# DCDC.net
KiCad netlist of a schematic drawn in EasyEDA Pro
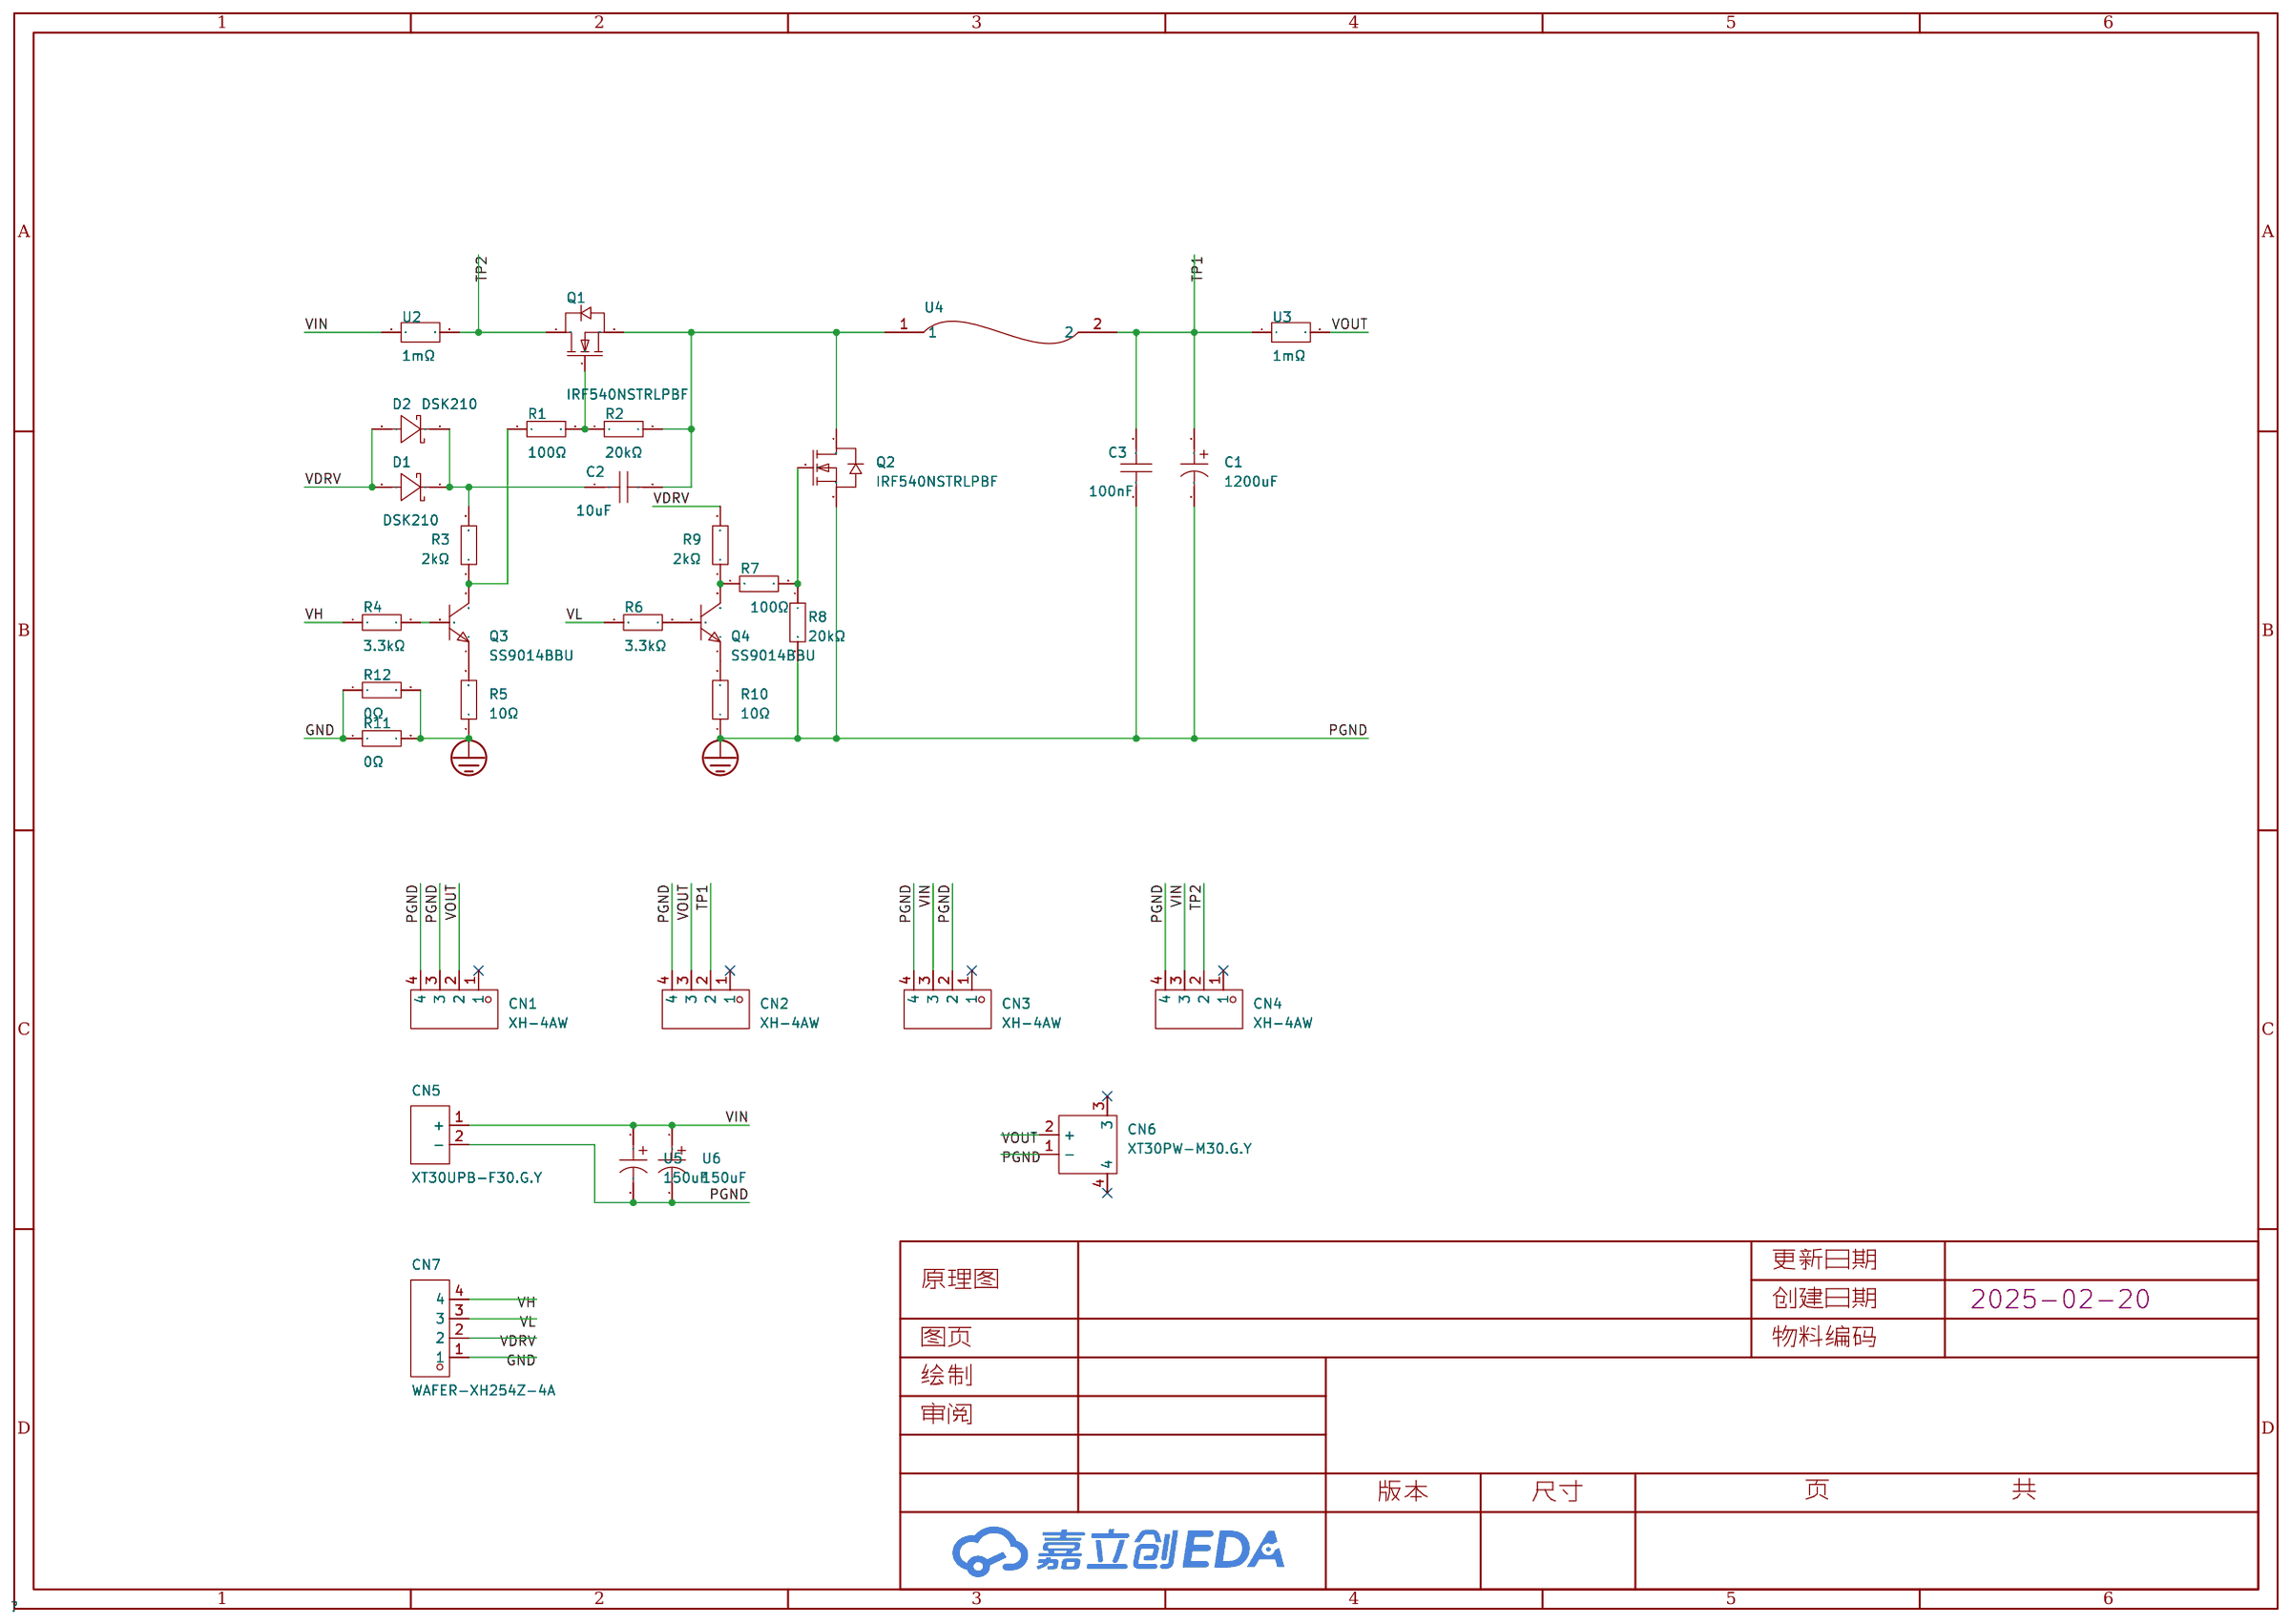
[diagram p0: schematic sheet]

(export (version "E")
  (design (tool "Eeschema 10.0.6"))
  (components
    (comp (ref "C1")
      (value "1200uF")
      (footprint "easyedapro:CAP-TH_BD18.0-P7.50-D0.8-FD")
      (description "容值:1200uF;精度:±20%;额定电压:63V;纹波电流:665mA@100kHz;等效串联电阻:160mΩ@100kHz;")
      (fields
        (field (name "Manufacturer Part") "NXA63V1200M18*31.5 LO")
        (field (name "Manufacturer") "SAMYOUNG(韩国三莹)")
      )
      (libsource (lib "easyedapro") (part "NXA63V1200M18*31.5 LO"))
    )
    (comp (ref "C2")
      (value "10uF")
      (footprint "easyedapro:C0805")
      (description "容值:10uF;精度:±10%;额定电压:50V;材质(温度系数):X5R;")
      (fields
        (field (name "Manufacturer Part") "GRM21BR61H106KE43L")
        (field (name "Manufacturer") "muRata(村田)")
      )
      (libsource (lib "easyedapro") (part "GRM21BR61H106KE43L"))
    )
    (comp (ref "C3")
      (value "100nF")
      (footprint "easyedapro:C0805")
      (description "容值:100nF;精度:±10%;额定电压:50V;材质(温度系数):X7R;")
      (fields
        (field (name "Manufacturer Part") "CC0805KRX7R9BB104")
        (field (name "Manufacturer") "YAGEO(国巨)")
      )
      (libsource (lib "easyedapro") (part "CC0805KRX7R9BB104"))
    )
    (comp (ref "CN1")
      (value "XH-4AW")
      (footprint "easyedapro:CONN-TH_XH-4AW")
      (fields (field (name "Manufacturer") "HCTL(华灿天禄)"))
      (libsource (lib "easyedapro") (part "XH-4AW_C2908613"))
    )
    (comp (ref "CN2")
      (value "XH-4AW")
      (footprint "easyedapro:CONN-TH_XH-4AW")
      (fields (field (name "Manufacturer") "HCTL(华灿天禄)"))
      (libsource (lib "easyedapro") (part "XH-4AW_C2908613"))
    )
    (comp (ref "CN3")
      (value "XH-4AW")
      (footprint "easyedapro:CONN-TH_XH-4AW")
      (fields (field (name "Manufacturer") "HCTL(华灿天禄)"))
      (libsource (lib "easyedapro") (part "XH-4AW_C2908613"))
    )
    (comp (ref "CN4")
      (value "XH-4AW")
      (footprint "easyedapro:CONN-TH_XH-4AW")
      (fields (field (name "Manufacturer") "HCTL(华灿天禄)"))
      (libsource (lib "easyedapro") (part "XH-4AW_C2908613"))
    )
    (comp (ref "CN5")
      (value "XT30UPB-F30.G.Y")
      (footprint "easyedapro:CONN-TH_XT30UPB-F")
      (description "类别:-;类型1:-;")
      (fields (field (name "Manufacturer") "AMASS(艾迈斯)"))
      (libsource (lib "easyedapro") (part "XT30UPB-F"))
    )
    (comp (ref "CN6")
      (value "XT30PW-M30.G.Y")
      (footprint "easyedapro:CONN-TH_XT30PW-M")
      (description "类别:-;类型1:-;")
      (fields (field (name "Manufacturer") "AMASS(艾迈斯)"))
      (libsource (lib "easyedapro") (part "XT30PW-M"))
    )
    (comp (ref "CN7")
      (value "WAFER-XH254Z-4A")
      (footprint "easyedapro:CONN-TH_XH-4A")
      (description "插针结构:1x4P;间距:2.54mm;安装方式:直插;参考系列:XH;总PIN数:4P;排数:1;每排PIN数:4;额定电流:3A;工作温度范围:-25°C~+85°C;")
      (fields (field (name "Manufacturer") "HANBO(汉博)"))
      (libsource (lib "easyedapro") (part "WAFER-XH254Z-4A"))
    )
    (comp (ref "D1")
      (value "DSK210")
      (footprint "easyedapro:SOD-123FL_L2.7-W1.8-LS3.8-RD")
      (description "二极管配置:独立式;正向压降(Vf):850mV@2A;直流反向耐压(Vr):100V;整流电流:2A;")
      (fields (field (name "Manufacturer") "宏迦橙"))
      (libsource (lib "easyedapro") (part "DSK210_C7502713"))
    )
    (comp (ref "D2")
      (value "DSK210")
      (footprint "easyedapro:SOD-123FL_L2.7-W1.8-LS3.8-RD")
      (description "二极管配置:独立式;正向压降(Vf):850mV@2A;直流反向耐压(Vr):100V;整流电流:2A;")
      (fields (field (name "Manufacturer") "宏迦橙"))
      (libsource (lib "easyedapro") (part "DSK210_C7502713"))
    )
    (comp (ref "Q1")
      (value "IRF540NSTRLPBF")
      (footprint "easyedapro:TO-263-2_L10.0-W9.1-P5.08-LS15.2-TL")
      (fields (field (name "Manufacturer") "Infineon(英飞凌)"))
      (libsource (lib "easyedapro") (part "IRF540NSTRLPBF"))
    )
    (comp (ref "Q2")
      (value "IRF540NSTRLPBF")
      (footprint "easyedapro:TO-263-2_L10.0-W9.1-P5.08-LS15.2-TL")
      (fields (field (name "Manufacturer") "Infineon(英飞凌)"))
      (libsource (lib "easyedapro") (part "IRF540NSTRLPBF"))
    )
    (comp (ref "Q3")
      (value "SS9014BBU")
      (footprint "easyedapro:TO-92-3_L4.8-W3.7-P1.27-L-1")
      (description "晶体管类型:NPN;集电极电流(Ic):100mA;集射极击穿电压(Vceo):45V;耗散功率(Pd):450mW;直流电流增益(hFE):100@1mA,5V;")
      (fields (field (name "Manufacturer") "onsemi(安森美)"))
      (libsource (lib "easyedapro") (part "SS9014BBU"))
    )
    (comp (ref "Q4")
      (value "SS9014BBU")
      (footprint "easyedapro:TO-92-3_L4.8-W3.7-P1.27-L-1")
      (description "晶体管类型:NPN;集电极电流(Ic):100mA;集射极击穿电压(Vceo):45V;耗散功率(Pd):450mW;直流电流增益(hFE):100@1mA,5V;")
      (fields (field (name "Manufacturer") "onsemi(安森美)"))
      (libsource (lib "easyedapro") (part "SS9014BBU"))
    )
    (comp (ref "R1")
      (value "100Ω")
      (footprint "easyedapro:R0805")
      (description "电阻类型:厚膜电阻;阻值:100Ω;精度:±1%;功率:125mW;最大工作电压:150V;温度系数:±100ppm/°C;")
      (fields
        (field (name "Manufacturer Part") "0805W8F1000T5E")
        (field (name "Manufacturer") "UNI-ROYAL(厚声)")
      )
      (libsource (lib "easyedapro") (part "0805W8F1000T5E"))
    )
    (comp (ref "R2")
      (value "20kΩ")
      (footprint "easyedapro:R0805")
      (description "电阻类型:厚膜电阻;阻值:20kΩ;精度:±1%;功率:125mW;最大工作电压:150V;温度系数:±100ppm/°C;")
      (fields
        (field (name "Manufacturer Part") "0805W8F2002T5E")
        (field (name "Manufacturer") "UNI-ROYAL(厚声)")
      )
      (libsource (lib "easyedapro") (part "0805W8F2002T5E"))
    )
    (comp (ref "R3")
      (value "2kΩ")
      (footprint "easyedapro:R0805")
      (description "电阻类型:厚膜电阻;阻值:2kΩ;精度:±1%;功率:125mW;最大工作电压:150V;温度系数:±100ppm/°C;")
      (fields
        (field (name "Manufacturer Part") "0805W8F2001T5E")
        (field (name "Manufacturer") "UNI-ROYAL(厚声)")
      )
      (libsource (lib "easyedapro") (part "0805W8F2001T5E"))
    )
    (comp (ref "R4")
      (value "3.3kΩ")
      (footprint "easyedapro:R0805")
      (description "电阻类型:厚膜电阻;阻值:3.3kΩ;精度:±1%;功率:125mW;最大工作电压:150V;温度系数:±100ppm/°C;")
      (fields
        (field (name "Manufacturer Part") "0805W8F3301T5E")
        (field (name "Manufacturer") "UNI-ROYAL(厚声)")
      )
      (libsource (lib "easyedapro") (part "0805W8F3301T5E"))
    )
    (comp (ref "R5")
      (value "10Ω")
      (footprint "easyedapro:R1206")
      (description "电阻类型:厚膜电阻;阻值:10Ω;精度:±1%;功率:250mW;最大工作电压:200V;温度系数:±400ppm/°C;")
      (fields
        (field (name "Manufacturer Part") "1206W4F100JT5E")
        (field (name "Manufacturer") "UNI-ROYAL(厚声)")
      )
      (libsource (lib "easyedapro") (part "1206W4F100JT5E"))
    )
    (comp (ref "R6")
      (value "3.3kΩ")
      (footprint "easyedapro:R0805")
      (description "电阻类型:厚膜电阻;阻值:3.3kΩ;精度:±1%;功率:125mW;最大工作电压:150V;温度系数:±100ppm/°C;")
      (fields
        (field (name "Manufacturer Part") "0805W8F3301T5E")
        (field (name "Manufacturer") "UNI-ROYAL(厚声)")
      )
      (libsource (lib "easyedapro") (part "0805W8F3301T5E"))
    )
    (comp (ref "R7")
      (value "100Ω")
      (footprint "easyedapro:R0805")
      (description "电阻类型:厚膜电阻;阻值:100Ω;精度:±1%;功率:125mW;最大工作电压:150V;温度系数:±100ppm/°C;")
      (fields
        (field (name "Manufacturer Part") "0805W8F1000T5E")
        (field (name "Manufacturer") "UNI-ROYAL(厚声)")
      )
      (libsource (lib "easyedapro") (part "0805W8F1000T5E"))
    )
    (comp (ref "R8")
      (value "20kΩ")
      (footprint "easyedapro:R0805")
      (description "电阻类型:厚膜电阻;阻值:20kΩ;精度:±1%;功率:125mW;最大工作电压:150V;温度系数:±100ppm/°C;")
      (fields
        (field (name "Manufacturer Part") "0805W8F2002T5E")
        (field (name "Manufacturer") "UNI-ROYAL(厚声)")
      )
      (libsource (lib "easyedapro") (part "0805W8F2002T5E"))
    )
    (comp (ref "R9")
      (value "2kΩ")
      (footprint "easyedapro:R0805")
      (description "电阻类型:厚膜电阻;阻值:2kΩ;精度:±1%;功率:125mW;最大工作电压:150V;温度系数:±100ppm/°C;")
      (fields
        (field (name "Manufacturer Part") "0805W8F2001T5E")
        (field (name "Manufacturer") "UNI-ROYAL(厚声)")
      )
      (libsource (lib "easyedapro") (part "0805W8F2001T5E"))
    )
    (comp (ref "R10")
      (value "10Ω")
      (footprint "easyedapro:R1206")
      (description "电阻类型:厚膜电阻;阻值:10Ω;精度:±1%;功率:250mW;最大工作电压:200V;温度系数:±400ppm/°C;")
      (fields
        (field (name "Manufacturer Part") "1206W4F100JT5E")
        (field (name "Manufacturer") "UNI-ROYAL(厚声)")
      )
      (libsource (lib "easyedapro") (part "1206W4F100JT5E"))
    )
    (comp (ref "R11")
      (value "0Ω")
      (footprint "easyedapro:R0805")
      (description "电阻类型:厚膜电阻;阻值:0Ω;精度:±1%;功率:125mW;最大工作电压:150V;温度系数:±800ppm/°C;")
      (fields
        (field (name "Manufacturer Part") "0805W8F0000T5E")
        (field (name "Manufacturer") "UNI-ROYAL(厚声)")
      )
      (libsource (lib "easyedapro") (part "0805W8F0000T5E"))
    )
    (comp (ref "R12")
      (value "0Ω")
      (footprint "easyedapro:R0805")
      (description "电阻类型:厚膜电阻;阻值:0Ω;精度:±1%;功率:125mW;最大工作电压:150V;温度系数:±800ppm/°C;")
      (fields
        (field (name "Manufacturer Part") "0805W8F0000T5E")
        (field (name "Manufacturer") "UNI-ROYAL(厚声)")
      )
      (libsource (lib "easyedapro") (part "0805W8F0000T5E"))
    )
    (comp (ref "U2")
      (value "1mΩ")
      (footprint "easyedapro:R2512")
      (description "电阻类型:合金电阻;阻值:1mΩ;精度:±1%;功率:6W;")
      (fields
        (field (name "Manufacturer Part") "PSRP25M6FR001")
        (field (name "Manufacturer") "prosemi(普罗森美)")
      )
      (libsource (lib "easyedapro") (part "PSRP25M6FR001"))
    )
    (comp (ref "U3")
      (value "1mΩ")
      (footprint "easyedapro:R2512")
      (description "电阻类型:合金电阻;阻值:1mΩ;精度:±1%;功率:6W;")
      (fields
        (field (name "Manufacturer Part") "PSRP25M6FR001")
        (field (name "Manufacturer") "prosemi(普罗森美)")
      )
      (libsource (lib "easyedapro") (part "PSRP25M6FR001"))
    )
    (comp (ref "U4")
      (value "~")
      (footprint "easyedapro:HLD2920")
      (libsource (lib "easyedapro") (part "功率电感"))
    )
    (comp (ref "U5")
      (value "150uF")
      (footprint "easyedapro:CAP-TH_BD18.0-P7.50-D0.8-FD")
      (description "容值:150uF;额定电压:400V;")
      (fields
        (field (name "Manufacturer Part") "CD1101572GM1836VFL")
        (field (name "Manufacturer") "HRK(鸿瑞凯电子)")
      )
      (libsource (lib "easyedapro") (part "CD1101572GM1836VFL"))
    )
    (comp (ref "U6")
      (value "150uF")
      (footprint "easyedapro:CAP-TH_BD18.0-P7.50-D0.8-FD")
      (description "容值:150uF;额定电压:400V;")
      (fields
        (field (name "Manufacturer Part") "CD1101572GM1836VFL")
        (field (name "Manufacturer") "HRK(鸿瑞凯电子)")
      )
      (libsource (lib "easyedapro") (part "CD1101572GM1836VFL"))
    )
  )
  (nets
    (net (code "1") (name "/GND") (class "Default")
      (node (ref "CN7") (pin "1") (pinfunction "1_1") (pintype "unspecified"))
      (node (ref "R11") (pin "1") (pinfunction "1_1") (pintype "input"))
      (node (ref "R12") (pin "1") (pinfunction "1_1") (pintype "input"))
    )
    (net (code "2") (name "/TP1") (class "Default")
      (node (ref "C1") (pin "1") (pinfunction "1_1") (pintype "input"))
      (node (ref "C3") (pin "2") (pinfunction "2_2") (pintype "unspecified"))
      (node (ref "CN2") (pin "2") (pinfunction "2_2") (pintype "unspecified"))
      (node (ref "U3") (pin "1") (pinfunction "1_1") (pintype "unspecified"))
      (node (ref "U4") (pin "2") (pinfunction "2_2") (pintype "input"))
    )
    (net (code "3") (name "/TP2") (class "Default")
      (node (ref "CN4") (pin "2") (pinfunction "2_2") (pintype "unspecified"))
      (node (ref "Q1") (pin "4") (pinfunction "D_4") (pintype "unspecified"))
      (node (ref "U2") (pin "2") (pinfunction "2_2") (pintype "unspecified"))
    )
    (net (code "4") (name "/VDRV") (class "Default")
      (node (ref "CN7") (pin "2") (pinfunction "2_2") (pintype "unspecified"))
      (node (ref "D1") (pin "2") (pinfunction "A_2") (pintype "unspecified"))
      (node (ref "D2") (pin "2") (pinfunction "A_2") (pintype "unspecified"))
      (node (ref "R9") (pin "2") (pinfunction "2_2") (pintype "input"))
    )
    (net (code "5") (name "/VH") (class "Default")
      (node (ref "CN7") (pin "4") (pinfunction "4_4") (pintype "unspecified"))
      (node (ref "R4") (pin "1") (pinfunction "1_1") (pintype "input"))
    )
    (net (code "6") (name "/VIN") (class "Default")
      (node (ref "CN3") (pin "3") (pinfunction "3_3") (pintype "unspecified"))
      (node (ref "CN4") (pin "3") (pinfunction "3_3") (pintype "unspecified"))
      (node (ref "CN5") (pin "1") (pinfunction "+_1") (pintype "unspecified"))
      (node (ref "U2") (pin "1") (pinfunction "1_1") (pintype "unspecified"))
      (node (ref "U5") (pin "1") (pinfunction "1_1") (pintype "input"))
      (node (ref "U6") (pin "1") (pinfunction "1_1") (pintype "input"))
    )
    (net (code "7") (name "/VL") (class "Default")
      (node (ref "CN7") (pin "3") (pinfunction "3_3") (pintype "unspecified"))
      (node (ref "R6") (pin "1") (pinfunction "1_1") (pintype "input"))
    )
    (net (code "8") (name "/VOUT") (class "Default")
      (node (ref "CN1") (pin "2") (pinfunction "2_2") (pintype "unspecified"))
      (node (ref "CN2") (pin "3") (pinfunction "3_3") (pintype "unspecified"))
      (node (ref "CN6") (pin "2") (pinfunction "+_2") (pintype "unspecified"))
      (node (ref "U3") (pin "2") (pinfunction "2_2") (pintype "unspecified"))
    )
    (net (code "9") (name "Net-(D1-K)") (class "Default")
      (node (ref "C2") (pin "1") (pinfunction "1_1") (pintype "unspecified"))
      (node (ref "D1") (pin "1") (pinfunction "K_1") (pintype "unspecified"))
      (node (ref "D2") (pin "1") (pinfunction "K_1") (pintype "unspecified"))
      (node (ref "R3") (pin "2") (pinfunction "2_2") (pintype "input"))
    )
    (net (code "10") (name "Net-(Q1-G)") (class "Default")
      (node (ref "Q1") (pin "1") (pinfunction "G_1") (pintype "unspecified"))
      (node (ref "R1") (pin "2") (pinfunction "2_2") (pintype "input"))
      (node (ref "R2") (pin "1") (pinfunction "1_1") (pintype "input"))
    )
    (net (code "11") (name "Net-(Q1-S)") (class "Default")
      (node (ref "C2") (pin "2") (pinfunction "2_2") (pintype "unspecified"))
      (node (ref "Q1") (pin "3") (pinfunction "S_3") (pintype "unspecified"))
      (node (ref "Q2") (pin "4") (pinfunction "D_4") (pintype "unspecified"))
      (node (ref "R2") (pin "2") (pinfunction "2_2") (pintype "input"))
      (node (ref "U4") (pin "1") (pinfunction "1_1") (pintype "input"))
    )
    (net (code "12") (name "Net-(Q2-G)") (class "Default")
      (node (ref "Q2") (pin "1") (pinfunction "G_1") (pintype "unspecified"))
      (node (ref "R7") (pin "2") (pinfunction "2_2") (pintype "input"))
      (node (ref "R8") (pin "1") (pinfunction "1_1") (pintype "input"))
    )
    (net (code "13") (name "Net-(Q3-B)") (class "Default")
      (node (ref "Q3") (pin "2") (pinfunction "B_2") (pintype "unspecified"))
      (node (ref "R4") (pin "2") (pinfunction "2_2") (pintype "input"))
    )
    (net (code "14") (name "Net-(Q3-C)") (class "Default")
      (node (ref "Q3") (pin "3") (pinfunction "C_3") (pintype "unspecified"))
      (node (ref "R1") (pin "1") (pinfunction "1_1") (pintype "input"))
      (node (ref "R3") (pin "1") (pinfunction "1_1") (pintype "input"))
    )
    (net (code "15") (name "Net-(Q3-E)") (class "Default")
      (node (ref "Q3") (pin "1") (pinfunction "E_1") (pintype "unspecified"))
      (node (ref "R5") (pin "2") (pinfunction "2_2") (pintype "input"))
    )
    (net (code "16") (name "Net-(Q4-B)") (class "Default")
      (node (ref "Q4") (pin "2") (pinfunction "B_2") (pintype "unspecified"))
      (node (ref "R6") (pin "2") (pinfunction "2_2") (pintype "input"))
    )
    (net (code "17") (name "Net-(Q4-C)") (class "Default")
      (node (ref "Q4") (pin "3") (pinfunction "C_3") (pintype "unspecified"))
      (node (ref "R7") (pin "1") (pinfunction "1_1") (pintype "input"))
      (node (ref "R9") (pin "1") (pinfunction "1_1") (pintype "input"))
    )
    (net (code "18") (name "Net-(Q4-E)") (class "Default")
      (node (ref "Q4") (pin "1") (pinfunction "E_1") (pintype "unspecified"))
      (node (ref "R10") (pin "2") (pinfunction "2_2") (pintype "input"))
    )
    (net (code "19") (name "PGND") (class "Default")
      (node (ref "C1") (pin "2") (pinfunction "2_2") (pintype "input"))
      (node (ref "C3") (pin "1") (pinfunction "1_1") (pintype "unspecified"))
      (node (ref "CN1") (pin "3") (pinfunction "3_3") (pintype "unspecified"))
      (node (ref "CN1") (pin "4") (pinfunction "4_4") (pintype "unspecified"))
      (node (ref "CN2") (pin "4") (pinfunction "4_4") (pintype "unspecified"))
      (node (ref "CN3") (pin "2") (pinfunction "2_2") (pintype "unspecified"))
      (node (ref "CN3") (pin "4") (pinfunction "4_4") (pintype "unspecified"))
      (node (ref "CN4") (pin "4") (pinfunction "4_4") (pintype "unspecified"))
      (node (ref "CN5") (pin "2") (pinfunction "-_2") (pintype "unspecified"))
      (node (ref "CN6") (pin "1") (pinfunction "-_1") (pintype "unspecified"))
      (node (ref "Q2") (pin "3") (pinfunction "S_3") (pintype "unspecified"))
      (node (ref "R10") (pin "1") (pinfunction "1_1") (pintype "input"))
      (node (ref "R11") (pin "2") (pinfunction "2_2") (pintype "input"))
      (node (ref "R12") (pin "2") (pinfunction "2_2") (pintype "input"))
      (node (ref "R5") (pin "1") (pinfunction "1_1") (pintype "input"))
      (node (ref "R8") (pin "2") (pinfunction "2_2") (pintype "input"))
      (node (ref "U5") (pin "2") (pinfunction "2_2") (pintype "input"))
      (node (ref "U6") (pin "2") (pinfunction "2_2") (pintype "input"))
    )
    (net (code "20") (name "unconnected-(CN1-Pad1)") (class "Default")
      (node (ref "CN1") (pin "1") (pinfunction "1_1") (pintype "unspecified+no_connect"))
    )
    (net (code "21") (name "unconnected-(CN2-Pad1)") (class "Default")
      (node (ref "CN2") (pin "1") (pinfunction "1_1") (pintype "unspecified+no_connect"))
    )
    (net (code "22") (name "unconnected-(CN3-Pad1)") (class "Default")
      (node (ref "CN3") (pin "1") (pinfunction "1_1") (pintype "unspecified+no_connect"))
    )
    (net (code "23") (name "unconnected-(CN4-Pad1)") (class "Default")
      (node (ref "CN4") (pin "1") (pinfunction "1_1") (pintype "unspecified+no_connect"))
    )
    (net (code "24") (name "unconnected-(CN6-Pad3)") (class "Default")
      (node (ref "CN6") (pin "3") (pinfunction "3_3") (pintype "unspecified+no_connect"))
    )
    (net (code "25") (name "unconnected-(CN6-Pad4)") (class "Default")
      (node (ref "CN6") (pin "4") (pinfunction "4_4") (pintype "unspecified+no_connect"))
    )
  )
)
